# saw_filter_pcb.net
KiCad netlist of a schematic drawn in Altium Designer
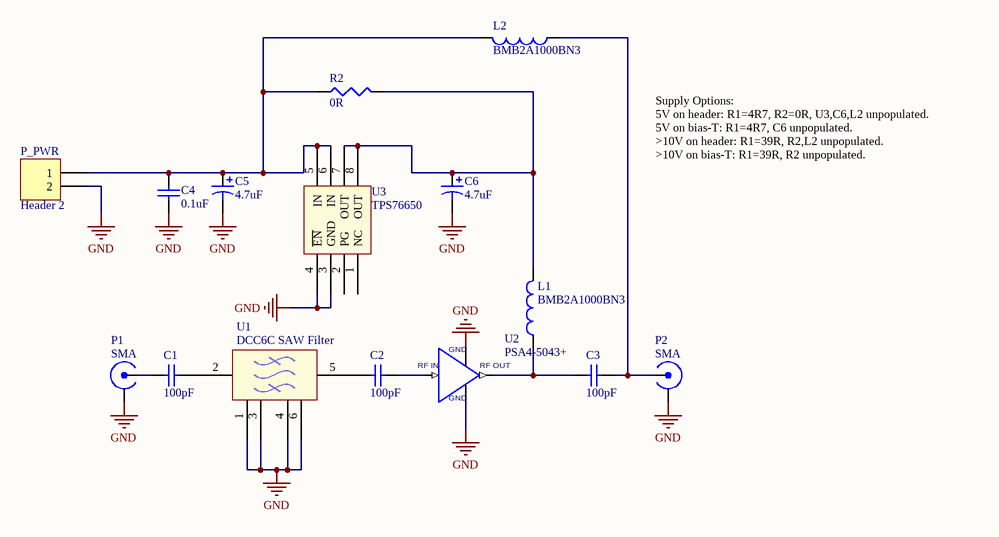
[diagram p0: saw_filter_pcb.SchDoc]

(export (version "E")
  (design (tool "Eeschema 10.0.6"))
  (components
    (comp (ref "C1")
      (value "100pF")
      (footprint "1608[0603]")
      (description "Capacitor (Semiconductor SIM Model)")
      (fields (field (name "Comment") "Cap Semi") (field (name "PUBLISHER") "Altium Limited"))
      (libsource (lib "Miscellaneous Devices") (part "Cap Semi"))
    )
    (comp (ref "C2")
      (value "100pF")
      (footprint "1608[0603]")
      (description "Capacitor (Semiconductor SIM Model)")
      (fields (field (name "Comment") "Cap Semi") (field (name "PUBLISHER") "Altium Limited"))
      (libsource (lib "Miscellaneous Devices") (part "Cap Semi"))
    )
    (comp (ref "C3")
      (value "100pF")
      (footprint "1608[0603]")
      (description "Capacitor (Semiconductor SIM Model)")
      (fields (field (name "Comment") "Cap Semi") (field (name "PUBLISHER") "Altium Limited"))
      (libsource (lib "Miscellaneous Devices") (part "Cap Semi"))
    )
    (comp (ref "C4")
      (value "0.1uF")
      (footprint "1608[0603]")
      (description "Capacitor (Semiconductor SIM Model)")
      (fields (field (name "Comment") "Cap Semi") (field (name "PUBLISHER") "Altium Limited"))
      (libsource (lib "Miscellaneous Devices") (part "Cap Semi"))
    )
    (comp (ref "C5")
      (value "4.7uF")
      (footprint "C0805")
      (description "Polarized Capacitor (Surface Mount)")
      (fields (field (name "Comment") "Cap Pol3") (field (name "PUBLISHER") "Altium Limited"))
      (libsource (lib "Miscellaneous Devices") (part "Cap Pol3"))
    )
    (comp (ref "C6")
      (value "4.7uF")
      (footprint "C0805")
      (description "Polarized Capacitor (Surface Mount)")
      (fields (field (name "Comment") "Cap Pol3") (field (name "PUBLISHER") "Altium Limited"))
      (libsource (lib "Miscellaneous Devices") (part "Cap Pol3"))
    )
    (comp (ref "L1")
      (value "BMB2A1000BN3")
      (footprint "6-0805_N")
      (description "Inductor")
      (fields (field (name "PUBLISHER") "Altium Limited"))
      (libsource (lib "Miscellaneous Devices") (part "Inductor"))
    )
    (comp (ref "L2")
      (value "BMB2A1000BN3")
      (footprint "6-0805_N")
      (description "Inductor")
      (fields (field (name "PUBLISHER") "Altium Limited"))
      (libsource (lib "Miscellaneous Devices") (part "Inductor"))
    )
    (comp (ref "P1")
      (value "SMA")
      (footprint "SMA_EDGE")
      (description "Power Connector")
      (fields (field (name "Comment") "SMA Con"))
      (libsource (lib "saw_filter_lib") (part "SMA Con"))
    )
    (comp (ref "P2")
      (value "SMA")
      (footprint "SMA_EDGE")
      (description "Power Connector")
      (fields (field (name "Comment") "SMA Con"))
      (libsource (lib "") (part "SMA Con_1"))
    )
    (comp (ref "P_PWR")
      (value "Header 2")
      (footprint "HDR1X2")
      (description "Header, 2-Pin")
      (fields (field (name "PUBLISHER") "Altium Limited"))
      (libsource (lib "Miscellaneous Connectors") (part "Header 2"))
    )
    (comp (ref "R2")
      (value "0R")
      (footprint "J1-0603")
      (description "Resistor")
      (fields (field (name "Comment") "Res3") (field (name "PUBLISHER") "Altium Limited"))
      (libsource (lib "Miscellaneous Devices") (part "Res3"))
    )
    (comp (ref "U1")
      (value "DCC6C SAW Filter")
      (footprint "DCC6C")
      (libsource (lib "saw_filter_lib") (part "DCC6C SAW Filter"))
    )
    (comp (ref "U2")
      (value "PSA4-5043+")
      (footprint "SOT-343_M")
      (libsource (lib "saw_filter_lib") (part "PSA4-5043+"))
    )
    (comp (ref "U3")
      (value "TPS76650")
      (footprint "TPS76633")
      (libsource (lib "saw_filter_lib") (part "TPS76650"))
    )
  )
  (nets
    (net (code "1") (name "GND") (class "Default")
      (node (ref "C4") (pin "1") (pinfunction "1_1") (pintype "passive"))
      (node (ref "C5") (pin "2") (pinfunction "2_2") (pintype "passive"))
      (node (ref "C6") (pin "2") (pinfunction "2_2") (pintype "passive"))
      (node (ref "P1") (pin "2") (pinfunction "2_2") (pintype "passive"))
      (node (ref "P2") (pin "2") (pinfunction "2_2") (pintype "passive"))
      (node (ref "P_PWR") (pin "2") (pinfunction "2_2") (pintype "passive"))
      (node (ref "U1") (pin "1") (pinfunction "IN_1") (pintype "passive"))
      (node (ref "U1") (pin "3") (pinfunction "IN_3") (pintype "passive"))
      (node (ref "U1") (pin "4") (pinfunction "IN_4") (pintype "passive"))
      (node (ref "U1") (pin "6") (pinfunction "IN_6") (pintype "passive"))
      (node (ref "U2") (pin "2") (pinfunction "GND_2") (pintype "power_in"))
      (node (ref "U2") (pin "4") (pinfunction "4_4") (pintype "passive"))
      (node (ref "U3") (pin "3") (pinfunction "GND_3") (pintype "passive"))
      (node (ref "U3") (pin "4") (pinfunction "~{EN}_4") (pintype "passive"))
    )
    (net (code "2") (name "Net-(C1-Pad1)") (class "Default")
      (node (ref "C1") (pin "1") (pinfunction "1_1") (pintype "passive"))
      (node (ref "P1") (pin "1") (pinfunction "1_1") (pintype "passive"))
    )
    (net (code "3") (name "Net-(C1-Pad2)") (class "Default")
      (node (ref "C1") (pin "2") (pinfunction "2_2") (pintype "passive"))
      (node (ref "U1") (pin "2") (pinfunction "IN_2") (pintype "passive"))
    )
    (net (code "4") (name "Net-(C2-Pad1)") (class "Default")
      (node (ref "C2") (pin "1") (pinfunction "1_1") (pintype "passive"))
      (node (ref "U1") (pin "5") (pinfunction "5_5") (pintype "passive"))
    )
    (net (code "5") (name "Net-(C3-Pad2)") (class "Default")
      (node (ref "C3") (pin "2") (pinfunction "2_2") (pintype "passive"))
      (node (ref "L2") (pin "1") (pinfunction "1_1") (pintype "passive"))
      (node (ref "P2") (pin "1") (pinfunction "1_1") (pintype "passive"))
    )
    (net (code "6") (name "Net-(C4-Pad2)") (class "Default")
      (node (ref "C4") (pin "2") (pinfunction "2_2") (pintype "passive"))
      (node (ref "C5") (pin "1") (pinfunction "1_1") (pintype "passive"))
      (node (ref "L2") (pin "2") (pinfunction "2_2") (pintype "passive"))
      (node (ref "P_PWR") (pin "1") (pinfunction "1_1") (pintype "passive"))
      (node (ref "R2") (pin "1") (pinfunction "1_1") (pintype "passive"))
      (node (ref "U3") (pin "5") (pinfunction "IN_5") (pintype "passive"))
      (node (ref "U3") (pin "6") (pinfunction "IN_6") (pintype "passive"))
    )
    (net (code "7") (name "Net-(C6-Pad1)") (class "Default")
      (node (ref "C6") (pin "1") (pinfunction "1_1") (pintype "passive"))
      (node (ref "L1") (pin "2") (pinfunction "2_2") (pintype "passive"))
      (node (ref "R2") (pin "2") (pinfunction "2_2") (pintype "passive"))
      (node (ref "U3") (pin "7") (pinfunction "OUT_7") (pintype "passive"))
      (node (ref "U3") (pin "8") (pinfunction "OUT_8") (pintype "passive"))
    )
    (net (code "8") (name "Net-(U2-RF-IN)") (class "Default")
      (node (ref "C2") (pin "2") (pinfunction "2_2") (pintype "passive"))
      (node (ref "U2") (pin "3") (pinfunction "RF-IN_3") (pintype "input"))
    )
    (net (code "9") (name "Net-(U2-RF-OUT)") (class "Default")
      (node (ref "C3") (pin "1") (pinfunction "1_1") (pintype "passive"))
      (node (ref "L1") (pin "1") (pinfunction "1_1") (pintype "passive"))
      (node (ref "U2") (pin "1") (pinfunction "RF-OUT_1") (pintype "output"))
    )
    (net (code "10") (name "unconnected-(U3-NC-Pad1)") (class "Default")
      (node (ref "U3") (pin "1") (pinfunction "NC_1") (pintype "passive"))
    )
    (net (code "11") (name "unconnected-(U3-PG-Pad2)") (class "Default")
      (node (ref "U3") (pin "2") (pinfunction "PG_2") (pintype "passive"))
    )
  )
)
